# LVDS_PHY.net
KiCad netlist of a schematic drawn in Altium Designer
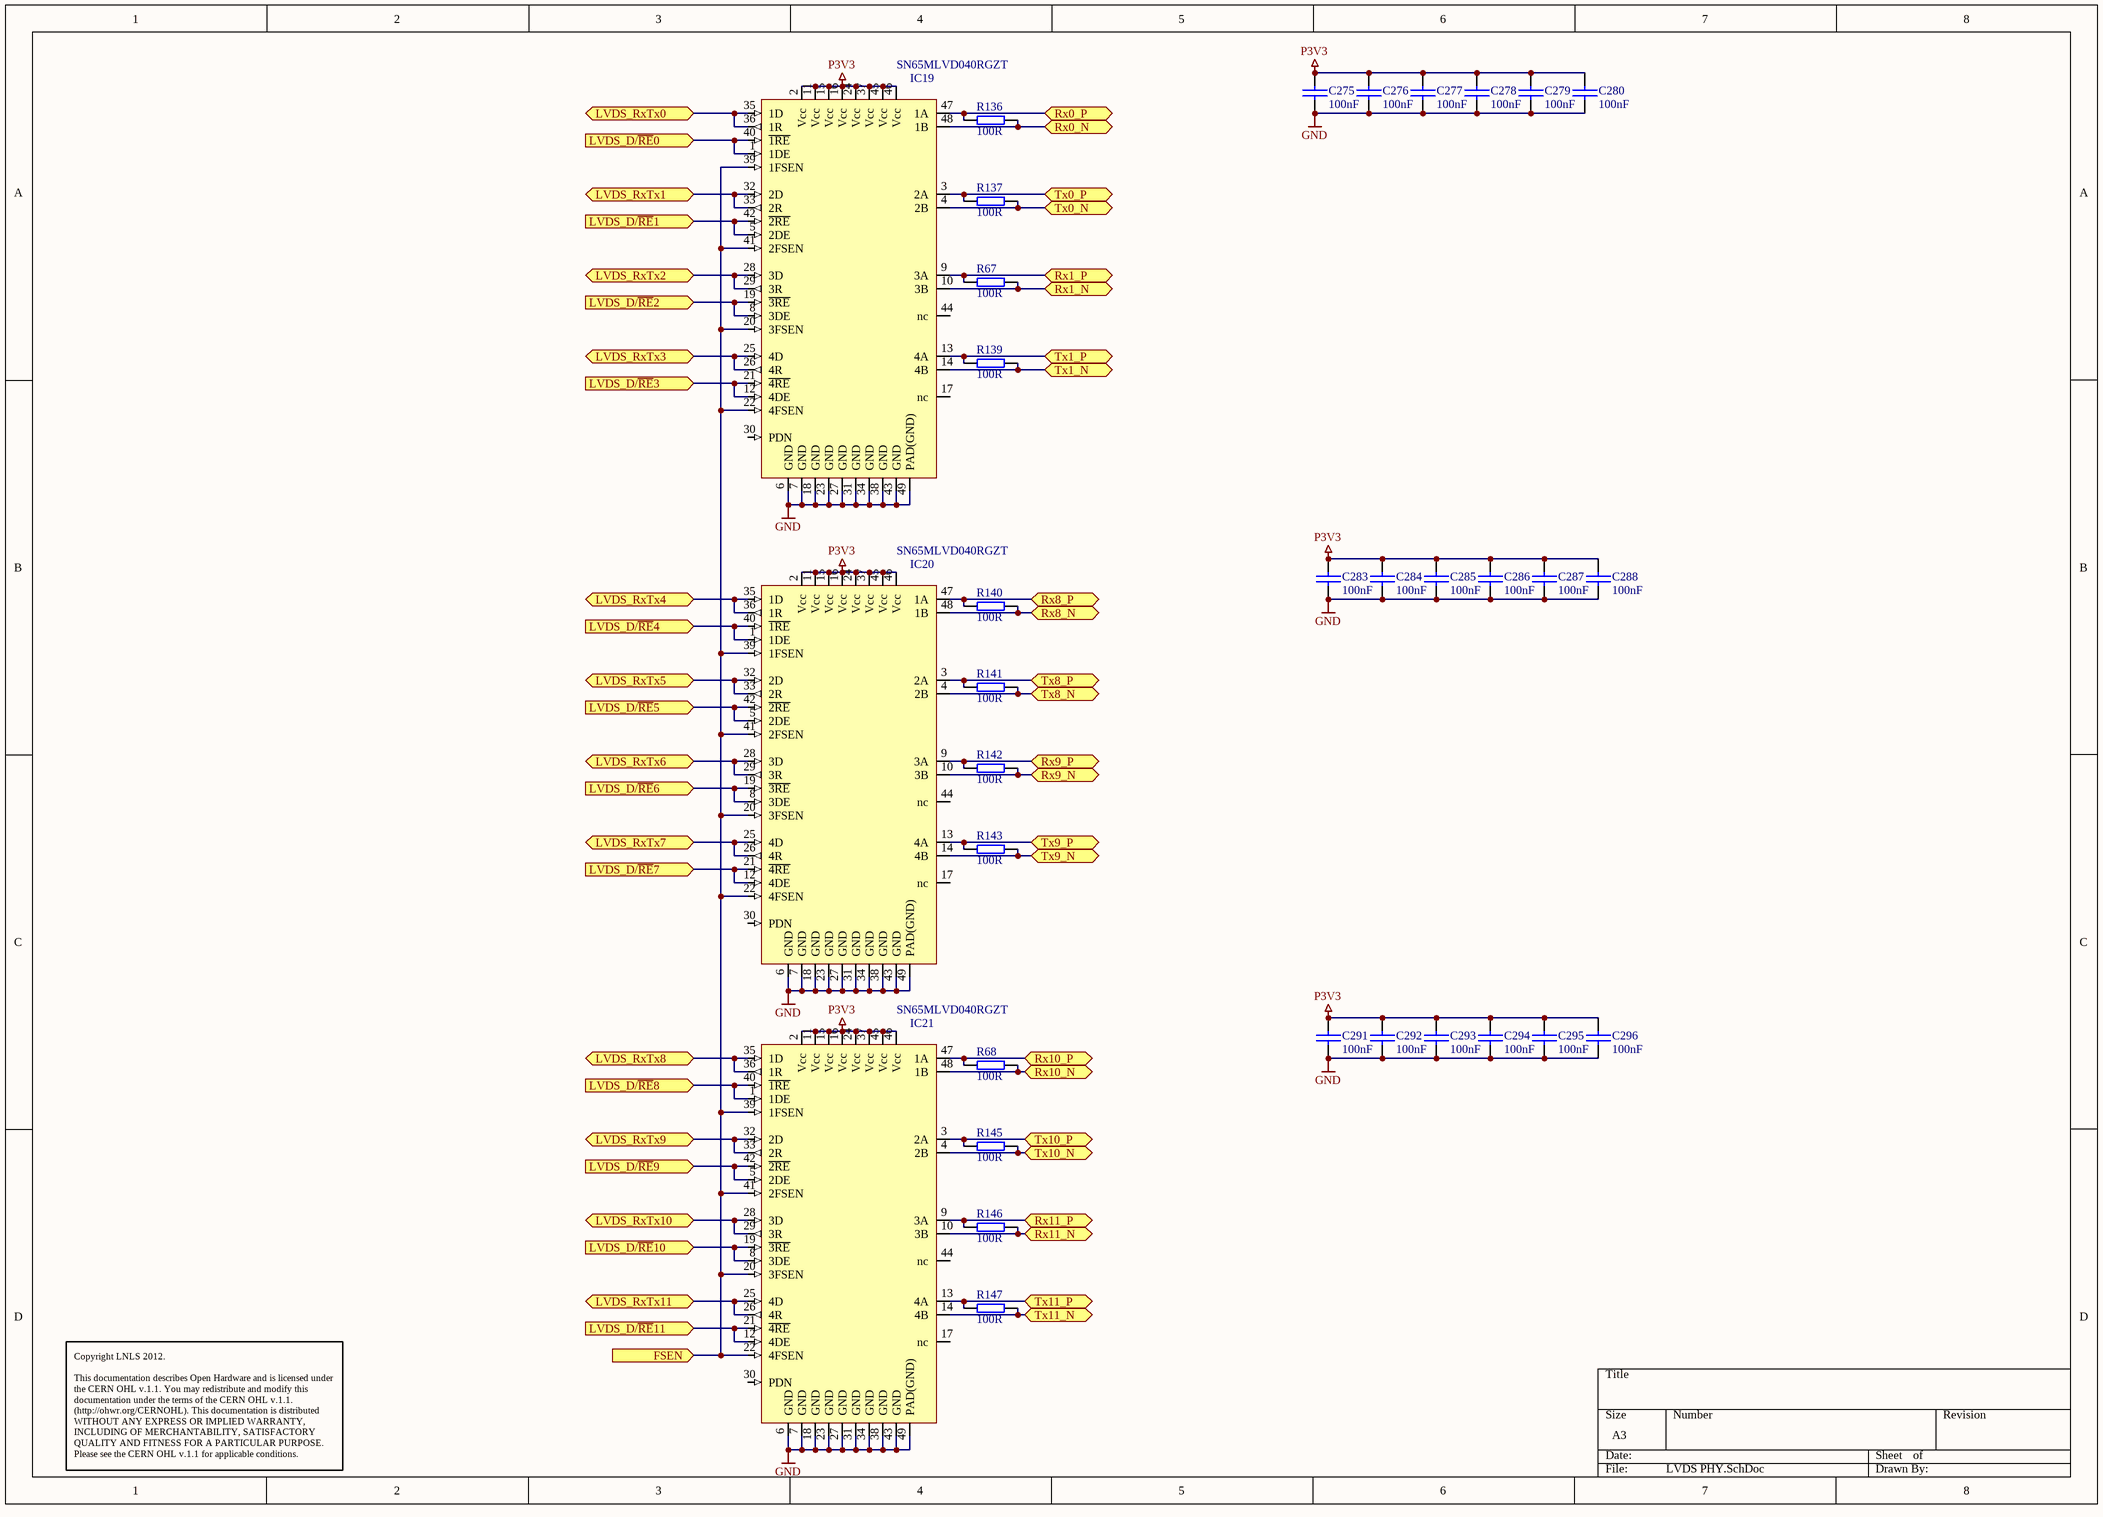
[diagram p0: LVDS PHY.SchDoc]

(export (version "E")
  (design (tool "Eeschema 10.0.6"))
  (components
    (comp (ref "C275")
      (value "100nF")
      (footprint "0201C")
      (description "Capacitor SMD")
      (libsource (lib "LIBRARY_SCH") (part "CAP_SMD_0201"))
    )
    (comp (ref "C276")
      (value "100nF")
      (footprint "0201C")
      (description "Capacitor SMD")
      (libsource (lib "LIBRARY_SCH") (part "CAP_SMD_0201"))
    )
    (comp (ref "C277")
      (value "100nF")
      (footprint "0201C")
      (description "Capacitor SMD")
      (libsource (lib "LIBRARY_SCH") (part "CAP_SMD_0201"))
    )
    (comp (ref "C278")
      (value "100nF")
      (footprint "0201C")
      (description "Capacitor SMD")
      (libsource (lib "LIBRARY_SCH") (part "CAP_SMD_0201"))
    )
    (comp (ref "C279")
      (value "100nF")
      (footprint "0201C")
      (description "Capacitor SMD")
      (libsource (lib "LIBRARY_SCH") (part "CAP_SMD_0201"))
    )
    (comp (ref "C280")
      (value "100nF")
      (footprint "0201C")
      (description "Capacitor SMD")
      (libsource (lib "LIBRARY_SCH") (part "CAP_SMD_0201"))
    )
    (comp (ref "C283")
      (value "100nF")
      (footprint "0201C")
      (description "Capacitor SMD")
      (libsource (lib "LIBRARY_SCH") (part "CAP_SMD_0201"))
    )
    (comp (ref "C284")
      (value "100nF")
      (footprint "0201C")
      (description "Capacitor SMD")
      (libsource (lib "LIBRARY_SCH") (part "CAP_SMD_0201"))
    )
    (comp (ref "C285")
      (value "100nF")
      (footprint "0201C")
      (description "Capacitor SMD")
      (libsource (lib "LIBRARY_SCH") (part "CAP_SMD_0201"))
    )
    (comp (ref "C286")
      (value "100nF")
      (footprint "0201C")
      (description "Capacitor SMD")
      (libsource (lib "LIBRARY_SCH") (part "CAP_SMD_0201"))
    )
    (comp (ref "C287")
      (value "100nF")
      (footprint "0201C")
      (description "Capacitor SMD")
      (libsource (lib "LIBRARY_SCH") (part "CAP_SMD_0201"))
    )
    (comp (ref "C288")
      (value "100nF")
      (footprint "0201C")
      (description "Capacitor SMD")
      (libsource (lib "LIBRARY_SCH") (part "CAP_SMD_0201"))
    )
    (comp (ref "C291")
      (value "100nF")
      (footprint "0201C")
      (description "Capacitor SMD")
      (libsource (lib "LIBRARY_SCH") (part "CAP_SMD_0201"))
    )
    (comp (ref "C292")
      (value "100nF")
      (footprint "0201C")
      (description "Capacitor SMD")
      (libsource (lib "LIBRARY_SCH") (part "CAP_SMD_0201"))
    )
    (comp (ref "C293")
      (value "100nF")
      (footprint "0201C")
      (description "Capacitor SMD")
      (libsource (lib "LIBRARY_SCH") (part "CAP_SMD_0201"))
    )
    (comp (ref "C294")
      (value "100nF")
      (footprint "0201C")
      (description "Capacitor SMD")
      (libsource (lib "LIBRARY_SCH") (part "CAP_SMD_0201"))
    )
    (comp (ref "C295")
      (value "100nF")
      (footprint "0201C")
      (description "Capacitor SMD")
      (libsource (lib "LIBRARY_SCH") (part "CAP_SMD_0201"))
    )
    (comp (ref "C296")
      (value "100nF")
      (footprint "0201C")
      (description "Capacitor SMD")
      (libsource (lib "LIBRARY_SCH") (part "CAP_SMD_0201"))
    )
    (comp (ref "IC19")
      (value "SN65MLVD040RGZT")
      (footprint "QFN48L")
      (libsource (lib "LIBRARY_SCH") (part "IFC_SN65MLVD040"))
    )
    (comp (ref "IC20")
      (value "SN65MLVD040RGZT")
      (footprint "QFN48L")
      (libsource (lib "LIBRARY_SCH") (part "IFC_SN65MLVD040"))
    )
    (comp (ref "IC21")
      (value "SN65MLVD040RGZT")
      (footprint "QFN48L")
      (libsource (lib "LIBRARY_SCH") (part "IFC_SN65MLVD040"))
    )
    (comp (ref "R67")
      (value "100R")
      (footprint "0402R")
      (description "SMD Resistor")
      (libsource (lib "LIBRARY_SCH") (part "RES_0402"))
    )
    (comp (ref "R68")
      (value "100R")
      (footprint "0402R")
      (description "SMD Resistor")
      (libsource (lib "LIBRARY_SCH") (part "RES_0402"))
    )
    (comp (ref "R136")
      (value "100R")
      (footprint "0402R")
      (description "SMD Resistor")
      (libsource (lib "LIBRARY_SCH") (part "RES_0402"))
    )
    (comp (ref "R137")
      (value "100R")
      (footprint "0402R")
      (description "SMD Resistor")
      (libsource (lib "LIBRARY_SCH") (part "RES_0402"))
    )
    (comp (ref "R139")
      (value "100R")
      (footprint "0402R")
      (description "SMD Resistor")
      (libsource (lib "LIBRARY_SCH") (part "RES_0402"))
    )
    (comp (ref "R140")
      (value "100R")
      (footprint "0402R")
      (description "SMD Resistor")
      (libsource (lib "LIBRARY_SCH") (part "RES_0402"))
    )
    (comp (ref "R141")
      (value "100R")
      (footprint "0402R")
      (description "SMD Resistor")
      (libsource (lib "LIBRARY_SCH") (part "RES_0402"))
    )
    (comp (ref "R142")
      (value "100R")
      (footprint "0402R")
      (description "SMD Resistor")
      (libsource (lib "LIBRARY_SCH") (part "RES_0402"))
    )
    (comp (ref "R143")
      (value "100R")
      (footprint "0402R")
      (description "SMD Resistor")
      (libsource (lib "LIBRARY_SCH") (part "RES_0402"))
    )
    (comp (ref "R145")
      (value "100R")
      (footprint "0402R")
      (description "SMD Resistor")
      (libsource (lib "LIBRARY_SCH") (part "RES_0402"))
    )
    (comp (ref "R146")
      (value "100R")
      (footprint "0402R")
      (description "SMD Resistor")
      (libsource (lib "LIBRARY_SCH") (part "RES_0402"))
    )
    (comp (ref "R147")
      (value "100R")
      (footprint "0402R")
      (description "SMD Resistor")
      (libsource (lib "LIBRARY_SCH") (part "RES_0402"))
    )
  )
  (nets
    (net (code "1") (name "/FSEN") (class "Default")
      (node (ref "IC19") (pin "20") (pinfunction "3FSEN_20") (pintype "input"))
      (node (ref "IC19") (pin "22") (pinfunction "4FSEN_22") (pintype "input"))
      (node (ref "IC19") (pin "39") (pinfunction "1FSEN_39") (pintype "input"))
      (node (ref "IC19") (pin "41") (pinfunction "2FSEN_41") (pintype "input"))
      (node (ref "IC20") (pin "20") (pinfunction "3FSEN_20") (pintype "input"))
      (node (ref "IC20") (pin "22") (pinfunction "4FSEN_22") (pintype "input"))
      (node (ref "IC20") (pin "39") (pinfunction "1FSEN_39") (pintype "input"))
      (node (ref "IC20") (pin "41") (pinfunction "2FSEN_41") (pintype "input"))
      (node (ref "IC21") (pin "20") (pinfunction "3FSEN_20") (pintype "input"))
      (node (ref "IC21") (pin "22") (pinfunction "4FSEN_22") (pintype "input"))
      (node (ref "IC21") (pin "39") (pinfunction "1FSEN_39") (pintype "input"))
      (node (ref "IC21") (pin "41") (pinfunction "2FSEN_41") (pintype "input"))
    )
    (net (code "2") (name "/LVDS_D{slash}~{RE}0") (class "Default")
      (node (ref "IC19") (pin "1") (pinfunction "1DE_1") (pintype "input"))
      (node (ref "IC19") (pin "40") (pinfunction "~{1RE}_40") (pintype "input"))
    )
    (net (code "3") (name "/LVDS_D{slash}~{RE}1") (class "Default")
      (node (ref "IC19") (pin "42") (pinfunction "~{2RE}_42") (pintype "input"))
      (node (ref "IC19") (pin "5") (pinfunction "2DE_5") (pintype "input"))
    )
    (net (code "4") (name "/LVDS_D{slash}~{RE}2") (class "Default")
      (node (ref "IC19") (pin "19") (pinfunction "~{3RE}_19") (pintype "input"))
      (node (ref "IC19") (pin "8") (pinfunction "3DE_8") (pintype "input"))
    )
    (net (code "5") (name "/LVDS_D{slash}~{RE}3") (class "Default")
      (node (ref "IC19") (pin "12") (pinfunction "4DE_12") (pintype "input"))
      (node (ref "IC19") (pin "21") (pinfunction "~{4RE}_21") (pintype "input"))
    )
    (net (code "6") (name "/LVDS_D{slash}~{RE}4") (class "Default")
      (node (ref "IC20") (pin "1") (pinfunction "1DE_1") (pintype "input"))
      (node (ref "IC20") (pin "40") (pinfunction "~{1RE}_40") (pintype "input"))
    )
    (net (code "7") (name "/LVDS_D{slash}~{RE}5") (class "Default")
      (node (ref "IC20") (pin "42") (pinfunction "~{2RE}_42") (pintype "input"))
      (node (ref "IC20") (pin "5") (pinfunction "2DE_5") (pintype "input"))
    )
    (net (code "8") (name "/LVDS_D{slash}~{RE}6") (class "Default")
      (node (ref "IC20") (pin "19") (pinfunction "~{3RE}_19") (pintype "input"))
      (node (ref "IC20") (pin "8") (pinfunction "3DE_8") (pintype "input"))
    )
    (net (code "9") (name "/LVDS_D{slash}~{RE}7") (class "Default")
      (node (ref "IC20") (pin "12") (pinfunction "4DE_12") (pintype "input"))
      (node (ref "IC20") (pin "21") (pinfunction "~{4RE}_21") (pintype "input"))
    )
    (net (code "10") (name "/LVDS_D{slash}~{RE}8") (class "Default")
      (node (ref "IC21") (pin "1") (pinfunction "1DE_1") (pintype "input"))
      (node (ref "IC21") (pin "40") (pinfunction "~{1RE}_40") (pintype "input"))
    )
    (net (code "11") (name "/LVDS_D{slash}~{RE}9") (class "Default")
      (node (ref "IC21") (pin "42") (pinfunction "~{2RE}_42") (pintype "input"))
      (node (ref "IC21") (pin "5") (pinfunction "2DE_5") (pintype "input"))
    )
    (net (code "12") (name "/LVDS_D{slash}~{RE}10") (class "Default")
      (node (ref "IC21") (pin "19") (pinfunction "~{3RE}_19") (pintype "input"))
      (node (ref "IC21") (pin "8") (pinfunction "3DE_8") (pintype "input"))
    )
    (net (code "13") (name "/LVDS_D{slash}~{RE}11") (class "Default")
      (node (ref "IC21") (pin "12") (pinfunction "4DE_12") (pintype "input"))
      (node (ref "IC21") (pin "21") (pinfunction "~{4RE}_21") (pintype "input"))
    )
    (net (code "14") (name "/LVDS_RxTx0") (class "Default")
      (node (ref "IC19") (pin "35") (pinfunction "1D_35") (pintype "input"))
      (node (ref "IC19") (pin "36") (pinfunction "1R_36") (pintype "output"))
    )
    (net (code "15") (name "/LVDS_RxTx1") (class "Default")
      (node (ref "IC19") (pin "32") (pinfunction "2D_32") (pintype "input"))
      (node (ref "IC19") (pin "33") (pinfunction "2R_33") (pintype "output"))
    )
    (net (code "16") (name "/LVDS_RxTx2") (class "Default")
      (node (ref "IC19") (pin "28") (pinfunction "3D_28") (pintype "input"))
      (node (ref "IC19") (pin "29") (pinfunction "3R_29") (pintype "output"))
    )
    (net (code "17") (name "/LVDS_RxTx3") (class "Default")
      (node (ref "IC19") (pin "25") (pinfunction "4D_25") (pintype "input"))
      (node (ref "IC19") (pin "26") (pinfunction "4R_26") (pintype "output"))
    )
    (net (code "18") (name "/LVDS_RxTx4") (class "Default")
      (node (ref "IC20") (pin "35") (pinfunction "1D_35") (pintype "input"))
      (node (ref "IC20") (pin "36") (pinfunction "1R_36") (pintype "output"))
    )
    (net (code "19") (name "/LVDS_RxTx5") (class "Default")
      (node (ref "IC20") (pin "32") (pinfunction "2D_32") (pintype "input"))
      (node (ref "IC20") (pin "33") (pinfunction "2R_33") (pintype "output"))
    )
    (net (code "20") (name "/LVDS_RxTx6") (class "Default")
      (node (ref "IC20") (pin "28") (pinfunction "3D_28") (pintype "input"))
      (node (ref "IC20") (pin "29") (pinfunction "3R_29") (pintype "output"))
    )
    (net (code "21") (name "/LVDS_RxTx7") (class "Default")
      (node (ref "IC20") (pin "25") (pinfunction "4D_25") (pintype "input"))
      (node (ref "IC20") (pin "26") (pinfunction "4R_26") (pintype "output"))
    )
    (net (code "22") (name "/LVDS_RxTx8") (class "Default")
      (node (ref "IC21") (pin "35") (pinfunction "1D_35") (pintype "input"))
      (node (ref "IC21") (pin "36") (pinfunction "1R_36") (pintype "output"))
    )
    (net (code "23") (name "/LVDS_RxTx9") (class "Default")
      (node (ref "IC21") (pin "32") (pinfunction "2D_32") (pintype "input"))
      (node (ref "IC21") (pin "33") (pinfunction "2R_33") (pintype "output"))
    )
    (net (code "24") (name "/LVDS_RxTx10") (class "Default")
      (node (ref "IC21") (pin "28") (pinfunction "3D_28") (pintype "input"))
      (node (ref "IC21") (pin "29") (pinfunction "3R_29") (pintype "output"))
    )
    (net (code "25") (name "/LVDS_RxTx11") (class "Default")
      (node (ref "IC21") (pin "25") (pinfunction "4D_25") (pintype "input"))
      (node (ref "IC21") (pin "26") (pinfunction "4R_26") (pintype "output"))
    )
    (net (code "26") (name "/Rx0_N") (class "Default")
      (node (ref "IC19") (pin "48") (pinfunction "1B_48") (pintype "bidirectional"))
      (node (ref "R136") (pin "2") (pinfunction "2_2") (pintype "passive"))
    )
    (net (code "27") (name "/Rx0_P") (class "Default")
      (node (ref "IC19") (pin "47") (pinfunction "1A_47") (pintype "bidirectional"))
      (node (ref "R136") (pin "1") (pinfunction "1_1") (pintype "passive"))
    )
    (net (code "28") (name "/Rx1_N") (class "Default")
      (node (ref "IC19") (pin "10") (pinfunction "3B_10") (pintype "bidirectional"))
      (node (ref "R67") (pin "2") (pinfunction "2_2") (pintype "passive"))
    )
    (net (code "29") (name "/Rx1_P") (class "Default")
      (node (ref "IC19") (pin "9") (pinfunction "3A_9") (pintype "bidirectional"))
      (node (ref "R67") (pin "1") (pinfunction "1_1") (pintype "passive"))
    )
    (net (code "30") (name "/Rx8_N") (class "Default")
      (node (ref "IC20") (pin "48") (pinfunction "1B_48") (pintype "bidirectional"))
      (node (ref "R140") (pin "2") (pinfunction "2_2") (pintype "passive"))
    )
    (net (code "31") (name "/Rx8_P") (class "Default")
      (node (ref "IC20") (pin "47") (pinfunction "1A_47") (pintype "bidirectional"))
      (node (ref "R140") (pin "1") (pinfunction "1_1") (pintype "passive"))
    )
    (net (code "32") (name "/Rx9_N") (class "Default")
      (node (ref "IC20") (pin "10") (pinfunction "3B_10") (pintype "bidirectional"))
      (node (ref "R142") (pin "2") (pinfunction "2_2") (pintype "passive"))
    )
    (net (code "33") (name "/Rx9_P") (class "Default")
      (node (ref "IC20") (pin "9") (pinfunction "3A_9") (pintype "bidirectional"))
      (node (ref "R142") (pin "1") (pinfunction "1_1") (pintype "passive"))
    )
    (net (code "34") (name "/Rx10_N") (class "Default")
      (node (ref "IC21") (pin "48") (pinfunction "1B_48") (pintype "bidirectional"))
      (node (ref "R68") (pin "2") (pinfunction "2_2") (pintype "passive"))
    )
    (net (code "35") (name "/Rx10_P") (class "Default")
      (node (ref "IC21") (pin "47") (pinfunction "1A_47") (pintype "bidirectional"))
      (node (ref "R68") (pin "1") (pinfunction "1_1") (pintype "passive"))
    )
    (net (code "36") (name "/Rx11_N") (class "Default")
      (node (ref "IC21") (pin "10") (pinfunction "3B_10") (pintype "bidirectional"))
      (node (ref "R146") (pin "2") (pinfunction "2_2") (pintype "passive"))
    )
    (net (code "37") (name "/Rx11_P") (class "Default")
      (node (ref "IC21") (pin "9") (pinfunction "3A_9") (pintype "bidirectional"))
      (node (ref "R146") (pin "1") (pinfunction "1_1") (pintype "passive"))
    )
    (net (code "38") (name "/Tx0_N") (class "Default")
      (node (ref "IC19") (pin "4") (pinfunction "2B_4") (pintype "bidirectional"))
      (node (ref "R137") (pin "2") (pinfunction "2_2") (pintype "passive"))
    )
    (net (code "39") (name "/Tx0_P") (class "Default")
      (node (ref "IC19") (pin "3") (pinfunction "2A_3") (pintype "bidirectional"))
      (node (ref "R137") (pin "1") (pinfunction "1_1") (pintype "passive"))
    )
    (net (code "40") (name "/Tx1_N") (class "Default")
      (node (ref "IC19") (pin "14") (pinfunction "4B_14") (pintype "bidirectional"))
      (node (ref "R139") (pin "2") (pinfunction "2_2") (pintype "passive"))
    )
    (net (code "41") (name "/Tx1_P") (class "Default")
      (node (ref "IC19") (pin "13") (pinfunction "4A_13") (pintype "bidirectional"))
      (node (ref "R139") (pin "1") (pinfunction "1_1") (pintype "passive"))
    )
    (net (code "42") (name "/Tx8_N") (class "Default")
      (node (ref "IC20") (pin "4") (pinfunction "2B_4") (pintype "bidirectional"))
      (node (ref "R141") (pin "2") (pinfunction "2_2") (pintype "passive"))
    )
    (net (code "43") (name "/Tx8_P") (class "Default")
      (node (ref "IC20") (pin "3") (pinfunction "2A_3") (pintype "bidirectional"))
      (node (ref "R141") (pin "1") (pinfunction "1_1") (pintype "passive"))
    )
    (net (code "44") (name "/Tx9_N") (class "Default")
      (node (ref "IC20") (pin "14") (pinfunction "4B_14") (pintype "bidirectional"))
      (node (ref "R143") (pin "2") (pinfunction "2_2") (pintype "passive"))
    )
    (net (code "45") (name "/Tx9_P") (class "Default")
      (node (ref "IC20") (pin "13") (pinfunction "4A_13") (pintype "bidirectional"))
      (node (ref "R143") (pin "1") (pinfunction "1_1") (pintype "passive"))
    )
    (net (code "46") (name "/Tx10_N") (class "Default")
      (node (ref "IC21") (pin "4") (pinfunction "2B_4") (pintype "bidirectional"))
      (node (ref "R145") (pin "2") (pinfunction "2_2") (pintype "passive"))
    )
    (net (code "47") (name "/Tx10_P") (class "Default")
      (node (ref "IC21") (pin "3") (pinfunction "2A_3") (pintype "bidirectional"))
      (node (ref "R145") (pin "1") (pinfunction "1_1") (pintype "passive"))
    )
    (net (code "48") (name "/Tx11_N") (class "Default")
      (node (ref "IC21") (pin "14") (pinfunction "4B_14") (pintype "bidirectional"))
      (node (ref "R147") (pin "2") (pinfunction "2_2") (pintype "passive"))
    )
    (net (code "49") (name "/Tx11_P") (class "Default")
      (node (ref "IC21") (pin "13") (pinfunction "4A_13") (pintype "bidirectional"))
      (node (ref "R147") (pin "1") (pinfunction "1_1") (pintype "passive"))
    )
    (net (code "50") (name "GND") (class "Default")
      (node (ref "C275") (pin "2") (pinfunction "2_2") (pintype "passive"))
      (node (ref "C276") (pin "2") (pinfunction "2_2") (pintype "passive"))
      (node (ref "C277") (pin "2") (pinfunction "2_2") (pintype "passive"))
      (node (ref "C278") (pin "2") (pinfunction "2_2") (pintype "passive"))
      (node (ref "C279") (pin "2") (pinfunction "2_2") (pintype "passive"))
      (node (ref "C280") (pin "2") (pinfunction "2_2") (pintype "passive"))
      (node (ref "C283") (pin "2") (pinfunction "2_2") (pintype "passive"))
      (node (ref "C284") (pin "2") (pinfunction "2_2") (pintype "passive"))
      (node (ref "C285") (pin "2") (pinfunction "2_2") (pintype "passive"))
      (node (ref "C286") (pin "2") (pinfunction "2_2") (pintype "passive"))
      (node (ref "C287") (pin "2") (pinfunction "2_2") (pintype "passive"))
      (node (ref "C288") (pin "2") (pinfunction "2_2") (pintype "passive"))
      (node (ref "C291") (pin "2") (pinfunction "2_2") (pintype "passive"))
      (node (ref "C292") (pin "2") (pinfunction "2_2") (pintype "passive"))
      (node (ref "C293") (pin "2") (pinfunction "2_2") (pintype "passive"))
      (node (ref "C294") (pin "2") (pinfunction "2_2") (pintype "passive"))
      (node (ref "C295") (pin "2") (pinfunction "2_2") (pintype "passive"))
      (node (ref "C296") (pin "2") (pinfunction "2_2") (pintype "passive"))
      (node (ref "IC19") (pin "18") (pinfunction "GND_18") (pintype "power_in"))
      (node (ref "IC19") (pin "23") (pinfunction "GND_23") (pintype "power_in"))
      (node (ref "IC19") (pin "27") (pinfunction "GND_27") (pintype "power_in"))
      (node (ref "IC19") (pin "31") (pinfunction "GND_31") (pintype "power_in"))
      (node (ref "IC19") (pin "34") (pinfunction "GND_34") (pintype "power_in"))
      (node (ref "IC19") (pin "38") (pinfunction "GND_38") (pintype "power_in"))
      (node (ref "IC19") (pin "43") (pinfunction "GND_43") (pintype "power_in"))
      (node (ref "IC19") (pin "49") (pinfunction "PAD(GND)_49") (pintype "power_in"))
      (node (ref "IC19") (pin "6") (pinfunction "GND_6") (pintype "power_in"))
      (node (ref "IC19") (pin "7") (pinfunction "GND_7") (pintype "power_in"))
      (node (ref "IC20") (pin "18") (pinfunction "GND_18") (pintype "power_in"))
      (node (ref "IC20") (pin "23") (pinfunction "GND_23") (pintype "power_in"))
      (node (ref "IC20") (pin "27") (pinfunction "GND_27") (pintype "power_in"))
      (node (ref "IC20") (pin "31") (pinfunction "GND_31") (pintype "power_in"))
      (node (ref "IC20") (pin "34") (pinfunction "GND_34") (pintype "power_in"))
      (node (ref "IC20") (pin "38") (pinfunction "GND_38") (pintype "power_in"))
      (node (ref "IC20") (pin "43") (pinfunction "GND_43") (pintype "power_in"))
      (node (ref "IC20") (pin "49") (pinfunction "PAD(GND)_49") (pintype "power_in"))
      (node (ref "IC20") (pin "6") (pinfunction "GND_6") (pintype "power_in"))
      (node (ref "IC20") (pin "7") (pinfunction "GND_7") (pintype "power_in"))
      (node (ref "IC21") (pin "18") (pinfunction "GND_18") (pintype "power_in"))
      (node (ref "IC21") (pin "23") (pinfunction "GND_23") (pintype "power_in"))
      (node (ref "IC21") (pin "27") (pinfunction "GND_27") (pintype "power_in"))
      (node (ref "IC21") (pin "31") (pinfunction "GND_31") (pintype "power_in"))
      (node (ref "IC21") (pin "34") (pinfunction "GND_34") (pintype "power_in"))
      (node (ref "IC21") (pin "38") (pinfunction "GND_38") (pintype "power_in"))
      (node (ref "IC21") (pin "43") (pinfunction "GND_43") (pintype "power_in"))
      (node (ref "IC21") (pin "49") (pinfunction "PAD(GND)_49") (pintype "power_in"))
      (node (ref "IC21") (pin "6") (pinfunction "GND_6") (pintype "power_in"))
      (node (ref "IC21") (pin "7") (pinfunction "GND_7") (pintype "power_in"))
    )
    (net (code "51") (name "P3V3") (class "Default")
      (node (ref "C275") (pin "1") (pinfunction "1_1") (pintype "passive"))
      (node (ref "C276") (pin "1") (pinfunction "1_1") (pintype "passive"))
      (node (ref "C277") (pin "1") (pinfunction "1_1") (pintype "passive"))
      (node (ref "C278") (pin "1") (pinfunction "1_1") (pintype "passive"))
      (node (ref "C279") (pin "1") (pinfunction "1_1") (pintype "passive"))
      (node (ref "C280") (pin "1") (pinfunction "1_1") (pintype "passive"))
      (node (ref "C283") (pin "1") (pinfunction "1_1") (pintype "passive"))
      (node (ref "C284") (pin "1") (pinfunction "1_1") (pintype "passive"))
      (node (ref "C285") (pin "1") (pinfunction "1_1") (pintype "passive"))
      (node (ref "C286") (pin "1") (pinfunction "1_1") (pintype "passive"))
      (node (ref "C287") (pin "1") (pinfunction "1_1") (pintype "passive"))
      (node (ref "C288") (pin "1") (pinfunction "1_1") (pintype "passive"))
      (node (ref "C291") (pin "1") (pinfunction "1_1") (pintype "passive"))
      (node (ref "C292") (pin "1") (pinfunction "1_1") (pintype "passive"))
      (node (ref "C293") (pin "1") (pinfunction "1_1") (pintype "passive"))
      (node (ref "C294") (pin "1") (pinfunction "1_1") (pintype "passive"))
      (node (ref "C295") (pin "1") (pinfunction "1_1") (pintype "passive"))
      (node (ref "C296") (pin "1") (pinfunction "1_1") (pintype "passive"))
      (node (ref "IC19") (pin "11") (pinfunction "Vcc_11") (pintype "power_in"))
      (node (ref "IC19") (pin "15") (pinfunction "Vcc_15") (pintype "power_in"))
      (node (ref "IC19") (pin "16") (pinfunction "Vcc_16") (pintype "power_in"))
      (node (ref "IC19") (pin "2") (pinfunction "Vcc_2") (pintype "power_in"))
      (node (ref "IC19") (pin "24") (pinfunction "Vcc_24") (pintype "power_in"))
      (node (ref "IC19") (pin "37") (pinfunction "Vcc_37") (pintype "power_in"))
      (node (ref "IC19") (pin "45") (pinfunction "Vcc_45") (pintype "power_in"))
      (node (ref "IC19") (pin "46") (pinfunction "Vcc_46") (pintype "power_in"))
      (node (ref "IC20") (pin "11") (pinfunction "Vcc_11") (pintype "power_in"))
      (node (ref "IC20") (pin "15") (pinfunction "Vcc_15") (pintype "power_in"))
      (node (ref "IC20") (pin "16") (pinfunction "Vcc_16") (pintype "power_in"))
      (node (ref "IC20") (pin "2") (pinfunction "Vcc_2") (pintype "power_in"))
      (node (ref "IC20") (pin "24") (pinfunction "Vcc_24") (pintype "power_in"))
      (node (ref "IC20") (pin "37") (pinfunction "Vcc_37") (pintype "power_in"))
      (node (ref "IC20") (pin "45") (pinfunction "Vcc_45") (pintype "power_in"))
      (node (ref "IC20") (pin "46") (pinfunction "Vcc_46") (pintype "power_in"))
      (node (ref "IC21") (pin "11") (pinfunction "Vcc_11") (pintype "power_in"))
      (node (ref "IC21") (pin "15") (pinfunction "Vcc_15") (pintype "power_in"))
      (node (ref "IC21") (pin "16") (pinfunction "Vcc_16") (pintype "power_in"))
      (node (ref "IC21") (pin "2") (pinfunction "Vcc_2") (pintype "power_in"))
      (node (ref "IC21") (pin "24") (pinfunction "Vcc_24") (pintype "power_in"))
      (node (ref "IC21") (pin "37") (pinfunction "Vcc_37") (pintype "power_in"))
      (node (ref "IC21") (pin "45") (pinfunction "Vcc_45") (pintype "power_in"))
      (node (ref "IC21") (pin "46") (pinfunction "Vcc_46") (pintype "power_in"))
    )
    (net (code "52") (name "unconnected-(IC19-PDN-Pad30)") (class "Default")
      (node (ref "IC19") (pin "30") (pinfunction "PDN_30") (pintype "input"))
    )
    (net (code "53") (name "unconnected-(IC19-nc-Pad17)") (class "Default")
      (node (ref "IC19") (pin "17") (pinfunction "nc_17") (pintype "passive"))
    )
    (net (code "54") (name "unconnected-(IC19-nc-Pad44)") (class "Default")
      (node (ref "IC19") (pin "44") (pinfunction "nc_44") (pintype "power_in"))
    )
    (net (code "55") (name "unconnected-(IC20-PDN-Pad30)") (class "Default")
      (node (ref "IC20") (pin "30") (pinfunction "PDN_30") (pintype "input"))
    )
    (net (code "56") (name "unconnected-(IC20-nc-Pad17)") (class "Default")
      (node (ref "IC20") (pin "17") (pinfunction "nc_17") (pintype "passive"))
    )
    (net (code "57") (name "unconnected-(IC20-nc-Pad44)") (class "Default")
      (node (ref "IC20") (pin "44") (pinfunction "nc_44") (pintype "power_in"))
    )
    (net (code "58") (name "unconnected-(IC21-PDN-Pad30)") (class "Default")
      (node (ref "IC21") (pin "30") (pinfunction "PDN_30") (pintype "input"))
    )
    (net (code "59") (name "unconnected-(IC21-nc-Pad17)") (class "Default")
      (node (ref "IC21") (pin "17") (pinfunction "nc_17") (pintype "passive"))
    )
    (net (code "60") (name "unconnected-(IC21-nc-Pad44)") (class "Default")
      (node (ref "IC21") (pin "44") (pinfunction "nc_44") (pintype "power_in"))
    )
  )
)
